# DIINproject.net
KiCad netlist of a schematic drawn in Altium Designer
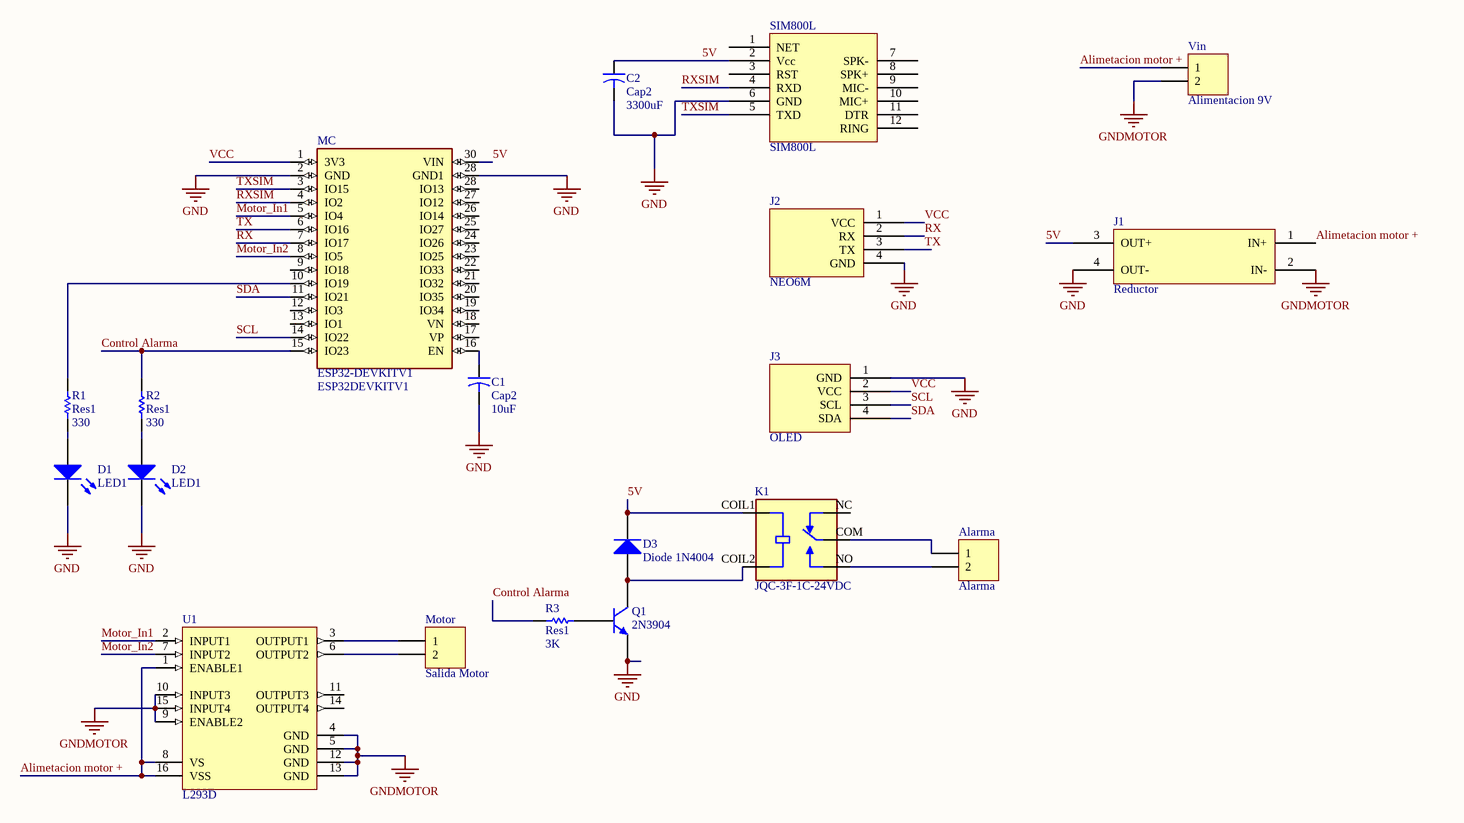
[diagram p0: DIINproject.SchDoc]

(export (version "E")
  (design (tool "Eeschema 10.0.6"))
  (components
    (comp (ref "Alarma")
      (value "Alarma")
      (footprint "HDR1X2")
      (description "Header, 2-Pin")
      (fields (field (name "PUBLISHER") "Altium Limited"))
      (libsource (lib "Miscellaneous Connectors") (part "Header 2"))
    )
    (comp (ref "C1")
      (value "Cap2")
      (footprint "CAPR5-4X5")
      (description "Capacitor")
      (fields (field (name "ALTIUM_VALUE") "10uF") (field (name "PUBLISHER") "Altium Limited"))
      (libsource (lib "Miscellaneous Devices") (part "Cap2"))
    )
    (comp (ref "C2")
      (value "Cap2")
      (footprint "CAPR5-4X5")
      (description "Capacitor")
      (fields (field (name "ALTIUM_VALUE") "3300uF") (field (name "PUBLISHER") "Altium Limited"))
      (libsource (lib "Miscellaneous Devices") (part "Cap2"))
    )
    (comp (ref "D1")
      (value "LED1")
      (footprint "LED-1")
      (description "Typical RED GaAs LED")
      (fields (field (name "PUBLISHER") "Altium Limited"))
      (libsource (lib "Miscellaneous Devices") (part "LED1"))
    )
    (comp (ref "D2")
      (value "LED1")
      (footprint "LED-1")
      (description "Typical RED GaAs LED")
      (fields (field (name "PUBLISHER") "Altium Limited"))
      (libsource (lib "Miscellaneous Devices") (part "LED1"))
    )
    (comp (ref "D3")
      (value "Diode 1N4004")
      (footprint "DO-41")
      (description "1 Amp General Purpose Rectifier")
      (fields (field (name "PUBLISHER") "Altium Limited"))
      (libsource (lib "Miscellaneous Devices") (part "Diode 1N4004"))
    )
    (comp (ref "J1") (value "Reductor") (footprint "Reductor") (libsource (lib "Modulos") (part "Reductor")))
    (comp (ref "J2") (value "NEO6M") (footprint "NEO6M") (libsource (lib "Modulos") (part "NEO6M")))
    (comp (ref "J3") (value "OLED") (footprint "OLED") (libsource (lib "Modulos") (part "OLED")))
    (comp (ref "K1")
      (value "JQC-3F-1C-24VDC")
      (footprint "RELAY_JQC-3F-1C-24VDC")
      (description "Miniature PCB Relay 24VDC, 10A 250VAC, 15A 125VAC, 10A 250VAC")
      (fields (field (name "MF") "YUEQING HENGWEI ELECTRONICS CO.,LTD."))
      (libsource (lib "JQC-3F-1C-24VDC") (part "JQC-3F-1C-24VDC"))
    )
    (comp (ref "MC")
      (value "ESP32DEVKITV1")
      (footprint "ESP32-DEVKITV1_3D")
      (fields (field (name "MF") "Do it") (field (name "MP") "ESP32 DEVKIT V1"))
      (libsource (lib "SchlibBruno") (part "ESP32DEVKITV1"))
    )
    (comp (ref "Motor")
      (value "Salida Motor")
      (footprint "HDR1X2")
      (description "Header, 2-Pin")
      (fields (field (name "PUBLISHER") "Altium Limited"))
      (libsource (lib "Miscellaneous Connectors") (part "Header 2"))
    )
    (comp (ref "Q1")
      (value "2N3904")
      (footprint "TO-92A")
      (description "NPN General Purpose Amplifier")
      (fields (field (name "PUBLISHER") "Altium Limited"))
      (libsource (lib "Miscellaneous Devices") (part "2N3904"))
    )
    (comp (ref "R1")
      (value "Res1")
      (footprint "AXIAL-0.3")
      (description "Resistor")
      (fields (field (name "ALTIUM_VALUE") "330") (field (name "PUBLISHER") "Altium Limited"))
      (libsource (lib "Miscellaneous Devices") (part "Res1"))
    )
    (comp (ref "R2")
      (value "Res1")
      (footprint "AXIAL-0.3")
      (description "Resistor")
      (fields (field (name "ALTIUM_VALUE") "330") (field (name "PUBLISHER") "Altium Limited"))
      (libsource (lib "Miscellaneous Devices") (part "Res1"))
    )
    (comp (ref "R3")
      (value "Res1")
      (footprint "AXIAL-0.3")
      (description "Resistor")
      (fields (field (name "ALTIUM_VALUE") "3K") (field (name "PUBLISHER") "Altium Limited"))
      (libsource (lib "Miscellaneous Devices") (part "Res1"))
    )
    (comp (ref "SIM800L")
      (value "SIM800L")
      (footprint "SIM800L")
      (libsource (lib "Modulos") (part "SIM800L"))
    )
    (comp (ref "U1")
      (value "L293D")
      (footprint "STM-L293D-16")
      (description "Push-Pull Four Channel Driver with Diode, 4.5 to 36 V, -40 to 150 degC, 16-Pin PDIP, RoHS, Tube")
      (fields (field (name "MANUFACTURER") "STMicroelectronics"))
      (libsource (lib "Altium Content Vault") (part "STM-L293D-16"))
    )
    (comp (ref "Vin")
      (value "Alimentacion 9V")
      (footprint "HDR1X2")
      (description "Header, 2-Pin")
      (fields (field (name "PUBLISHER") "Altium Limited"))
      (libsource (lib "Miscellaneous Connectors") (part "Header 2"))
    )
  )
  (nets
    (net (code "1") (name "/5V") (class "Default")
      (node (ref "C2") (pin "1") (pinfunction "1_1") (pintype "passive"))
      (node (ref "D3") (pin "2") (pinfunction "K_2") (pintype "passive"))
      (node (ref "J1") (pin "3") (pinfunction "OUT+_3") (pintype "passive"))
      (node (ref "K1") (pin "COIL1") (pinfunction "COIL1_COIL1") (pintype "passive"))
      (node (ref "MC") (pin "30") (pinfunction "VIN_30") (pintype "bidirectional"))
      (node (ref "SIM800L") (pin "2") (pinfunction "Vcc_2") (pintype "passive"))
    )
    (net (code "2") (name "/Alimetacion motor +") (class "Default")
      (node (ref "J1") (pin "1") (pinfunction "IN+_1") (pintype "passive"))
      (node (ref "U1") (pin "1") (pinfunction "ENABLE1_1") (pintype "input"))
      (node (ref "U1") (pin "16") (pinfunction "VSS_16") (pintype "power_in"))
      (node (ref "U1") (pin "8") (pinfunction "VS_8") (pintype "power_in"))
      (node (ref "Vin") (pin "1") (pinfunction "1_1") (pintype "passive"))
    )
    (net (code "3") (name "/Control Alarma") (class "Default")
      (node (ref "MC") (pin "15") (pinfunction "IO23_15") (pintype "bidirectional"))
      (node (ref "R2") (pin "1") (pinfunction "1_1") (pintype "passive"))
      (node (ref "R3") (pin "1") (pinfunction "1_1") (pintype "passive"))
    )
    (net (code "4") (name "/Motor_In1") (class "Default")
      (node (ref "MC") (pin "5") (pinfunction "IO4_5") (pintype "bidirectional"))
      (node (ref "U1") (pin "2") (pinfunction "INPUT1_2") (pintype "input"))
    )
    (net (code "5") (name "/Motor_In2") (class "Default")
      (node (ref "MC") (pin "8") (pinfunction "IO5_8") (pintype "bidirectional"))
      (node (ref "U1") (pin "7") (pinfunction "INPUT2_7") (pintype "input"))
    )
    (net (code "6") (name "/RX") (class "Default")
      (node (ref "J2") (pin "2") (pinfunction "RX_2") (pintype "passive"))
      (node (ref "MC") (pin "7") (pinfunction "IO17_7") (pintype "bidirectional"))
    )
    (net (code "7") (name "/RXSIM") (class "Default")
      (node (ref "MC") (pin "4") (pinfunction "IO2_4") (pintype "bidirectional"))
      (node (ref "SIM800L") (pin "4") (pinfunction "RXD_4") (pintype "passive"))
    )
    (net (code "8") (name "/SCL") (class "Default")
      (node (ref "J3") (pin "3") (pinfunction "SCL_3") (pintype "passive"))
      (node (ref "MC") (pin "14") (pinfunction "IO22_14") (pintype "bidirectional"))
    )
    (net (code "9") (name "/SDA") (class "Default")
      (node (ref "J3") (pin "4") (pinfunction "SDA_4") (pintype "passive"))
      (node (ref "MC") (pin "11") (pinfunction "IO21_11") (pintype "bidirectional"))
    )
    (net (code "10") (name "/TX") (class "Default")
      (node (ref "J2") (pin "3") (pinfunction "TX_3") (pintype "passive"))
      (node (ref "MC") (pin "6") (pinfunction "IO16_6") (pintype "bidirectional"))
    )
    (net (code "11") (name "/TXSIM") (class "Default")
      (node (ref "MC") (pin "3") (pinfunction "IO15_3") (pintype "bidirectional"))
      (node (ref "SIM800L") (pin "5") (pinfunction "TXD_5") (pintype "passive"))
    )
    (net (code "12") (name "/VCC") (class "Default")
      (node (ref "J2") (pin "1") (pinfunction "VCC_1") (pintype "passive"))
      (node (ref "J3") (pin "2") (pinfunction "VCC_2") (pintype "passive"))
      (node (ref "MC") (pin "1") (pinfunction "3V3_1") (pintype "bidirectional"))
    )
    (net (code "13") (name "GND") (class "Default")
      (node (ref "C1") (pin "2") (pinfunction "2_2") (pintype "passive"))
      (node (ref "C2") (pin "2") (pinfunction "2_2") (pintype "passive"))
      (node (ref "D1") (pin "2") (pinfunction "K_2") (pintype "passive"))
      (node (ref "D2") (pin "2") (pinfunction "K_2") (pintype "passive"))
      (node (ref "J1") (pin "4") (pinfunction "OUT-_4") (pintype "passive"))
      (node (ref "J2") (pin "4") (pinfunction "GND_4") (pintype "passive"))
      (node (ref "J3") (pin "1") (pinfunction "GND_1") (pintype "passive"))
      (node (ref "MC") (pin "2") (pinfunction "GND_2") (pintype "bidirectional"))
      (node (ref "MC") (pin "28") (pinfunction "GND1_28") (pintype "bidirectional"))
      (node (ref "Q1") (pin "1") (pinfunction "E_1") (pintype "passive"))
      (node (ref "SIM800L") (pin "6") (pinfunction "GND_6") (pintype "passive"))
    )
    (net (code "14") (name "GNDMOTOR") (class "Default")
      (node (ref "J1") (pin "2") (pinfunction "IN-_2") (pintype "passive"))
      (node (ref "U1") (pin "10") (pinfunction "INPUT3_10") (pintype "input"))
      (node (ref "U1") (pin "12") (pinfunction "GND_12") (pintype "power_in"))
      (node (ref "U1") (pin "13") (pinfunction "GND_13") (pintype "power_in"))
      (node (ref "U1") (pin "15") (pinfunction "INPUT4_15") (pintype "input"))
      (node (ref "U1") (pin "4") (pinfunction "GND_4") (pintype "power_in"))
      (node (ref "U1") (pin "5") (pinfunction "GND_5") (pintype "power_in"))
      (node (ref "U1") (pin "9") (pinfunction "ENABLE2_9") (pintype "input"))
      (node (ref "Vin") (pin "2") (pinfunction "2_2") (pintype "passive"))
    )
    (net (code "15") (name "Net-(Alarma-Pad1)") (class "Default")
      (node (ref "Alarma") (pin "1") (pinfunction "1_1") (pintype "passive"))
      (node (ref "K1") (pin "COM") (pinfunction "COM_COM") (pintype "passive"))
    )
    (net (code "16") (name "Net-(Alarma-Pad2)") (class "Default")
      (node (ref "Alarma") (pin "2") (pinfunction "2_2") (pintype "passive"))
      (node (ref "K1") (pin "NO") (pinfunction "NO_NO") (pintype "passive"))
    )
    (net (code "17") (name "Net-(D1-A)") (class "Default")
      (node (ref "D1") (pin "1") (pinfunction "A_1") (pintype "passive"))
      (node (ref "R1") (pin "1") (pinfunction "1_1") (pintype "passive"))
    )
    (net (code "18") (name "Net-(D2-A)") (class "Default")
      (node (ref "D2") (pin "1") (pinfunction "A_1") (pintype "passive"))
      (node (ref "R2") (pin "2") (pinfunction "2_2") (pintype "passive"))
    )
    (net (code "19") (name "Net-(D3-A)") (class "Default")
      (node (ref "D3") (pin "1") (pinfunction "A_1") (pintype "passive"))
      (node (ref "K1") (pin "COIL2") (pinfunction "COIL2_COIL2") (pintype "passive"))
      (node (ref "Q1") (pin "3") (pinfunction "C_3") (pintype "passive"))
    )
    (net (code "20") (name "Net-(MC-EN)") (class "Default")
      (node (ref "C1") (pin "1") (pinfunction "1_1") (pintype "passive"))
      (node (ref "MC") (pin "16") (pinfunction "EN_16") (pintype "bidirectional"))
    )
    (net (code "21") (name "Net-(MC-IO19)") (class "Default")
      (node (ref "MC") (pin "10") (pinfunction "IO19_10") (pintype "bidirectional"))
      (node (ref "R1") (pin "2") (pinfunction "2_2") (pintype "passive"))
    )
    (net (code "22") (name "Net-(Q1-B)") (class "Default")
      (node (ref "Q1") (pin "2") (pinfunction "B_2") (pintype "passive"))
      (node (ref "R3") (pin "2") (pinfunction "2_2") (pintype "passive"))
    )
    (net (code "23") (name "Net-(U1-OUTPUT1)") (class "Default")
      (node (ref "Motor") (pin "1") (pinfunction "1_1") (pintype "passive"))
      (node (ref "U1") (pin "3") (pinfunction "OUTPUT1_3") (pintype "output"))
    )
    (net (code "24") (name "Net-(U1-OUTPUT2)") (class "Default")
      (node (ref "Motor") (pin "2") (pinfunction "2_2") (pintype "passive"))
      (node (ref "U1") (pin "6") (pinfunction "OUTPUT2_6") (pintype "output"))
    )
    (net (code "25") (name "unconnected-(K1-PadNC)") (class "Default")
      (node (ref "K1") (pin "NC") (pinfunction "NC_NC") (pintype "passive"))
    )
    (net (code "26") (name "unconnected-(MC-IO1-Pad13)") (class "Default")
      (node (ref "MC") (pin "13") (pinfunction "IO1_13") (pintype "bidirectional"))
    )
    (net (code "27") (name "unconnected-(MC-IO3-Pad12)") (class "Default")
      (node (ref "MC") (pin "12") (pinfunction "IO3_12") (pintype "bidirectional"))
    )
    (net (code "28") (name "unconnected-(MC-IO12-Pad27)") (class "Default")
      (node (ref "MC") (pin "27") (pinfunction "IO12_27") (pintype "bidirectional"))
    )
    (net (code "29") (name "unconnected-(MC-IO13-Pad28)") (class "Default")
      (node (ref "MC") (pin "28") (pinfunction "IO13_28") (pintype "bidirectional"))
    )
    (net (code "30") (name "unconnected-(MC-IO14-Pad26)") (class "Default")
      (node (ref "MC") (pin "26") (pinfunction "IO14_26") (pintype "bidirectional"))
    )
    (net (code "31") (name "unconnected-(MC-IO18-Pad9)") (class "Default")
      (node (ref "MC") (pin "9") (pinfunction "IO18_9") (pintype "bidirectional"))
    )
    (net (code "32") (name "unconnected-(MC-IO25-Pad23)") (class "Default")
      (node (ref "MC") (pin "23") (pinfunction "IO25_23") (pintype "bidirectional"))
    )
    (net (code "33") (name "unconnected-(MC-IO26-Pad24)") (class "Default")
      (node (ref "MC") (pin "24") (pinfunction "IO26_24") (pintype "bidirectional"))
    )
    (net (code "34") (name "unconnected-(MC-IO27-Pad25)") (class "Default")
      (node (ref "MC") (pin "25") (pinfunction "IO27_25") (pintype "bidirectional"))
    )
    (net (code "35") (name "unconnected-(MC-IO32-Pad21)") (class "Default")
      (node (ref "MC") (pin "21") (pinfunction "IO32_21") (pintype "bidirectional"))
    )
    (net (code "36") (name "unconnected-(MC-IO33-Pad22)") (class "Default")
      (node (ref "MC") (pin "22") (pinfunction "IO33_22") (pintype "bidirectional"))
    )
    (net (code "37") (name "unconnected-(MC-IO34-Pad19)") (class "Default")
      (node (ref "MC") (pin "19") (pinfunction "IO34_19") (pintype "bidirectional"))
    )
    (net (code "38") (name "unconnected-(MC-IO35-Pad20)") (class "Default")
      (node (ref "MC") (pin "20") (pinfunction "IO35_20") (pintype "bidirectional"))
    )
    (net (code "39") (name "unconnected-(MC-VN-Pad18)") (class "Default")
      (node (ref "MC") (pin "18") (pinfunction "VN_18") (pintype "bidirectional"))
    )
    (net (code "40") (name "unconnected-(MC-VP-Pad17)") (class "Default")
      (node (ref "MC") (pin "17") (pinfunction "VP_17") (pintype "bidirectional"))
    )
    (net (code "41") (name "unconnected-(SIM800L-DTR-Pad11)") (class "Default")
      (node (ref "SIM800L") (pin "11") (pinfunction "DTR_11") (pintype "passive"))
    )
    (net (code "42") (name "unconnected-(SIM800L-MIC+-Pad10)") (class "Default")
      (node (ref "SIM800L") (pin "10") (pinfunction "MIC+_10") (pintype "passive"))
    )
    (net (code "43") (name "unconnected-(SIM800L-MIC--Pad9)") (class "Default")
      (node (ref "SIM800L") (pin "9") (pinfunction "MIC-_9") (pintype "passive"))
    )
    (net (code "44") (name "unconnected-(SIM800L-NET-Pad1)") (class "Default")
      (node (ref "SIM800L") (pin "1") (pinfunction "NET_1") (pintype "passive"))
    )
    (net (code "45") (name "unconnected-(SIM800L-RING-Pad12)") (class "Default")
      (node (ref "SIM800L") (pin "12") (pinfunction "RING_12") (pintype "passive"))
    )
    (net (code "46") (name "unconnected-(SIM800L-RST-Pad3)") (class "Default")
      (node (ref "SIM800L") (pin "3") (pinfunction "RST_3") (pintype "passive"))
    )
    (net (code "47") (name "unconnected-(SIM800L-SPK+-Pad8)") (class "Default")
      (node (ref "SIM800L") (pin "8") (pinfunction "SPK+_8") (pintype "passive"))
    )
    (net (code "48") (name "unconnected-(SIM800L-SPK--Pad7)") (class "Default")
      (node (ref "SIM800L") (pin "7") (pinfunction "SPK-_7") (pintype "passive"))
    )
    (net (code "49") (name "unconnected-(U1-OUTPUT3-Pad11)") (class "Default")
      (node (ref "U1") (pin "11") (pinfunction "OUTPUT3_11") (pintype "output"))
    )
    (net (code "50") (name "unconnected-(U1-OUTPUT4-Pad14)") (class "Default")
      (node (ref "U1") (pin "14") (pinfunction "OUTPUT4_14") (pintype "output"))
    )
  )
)
